# vcfvca.net
KiCad netlist of a schematic drawn in EAGLE
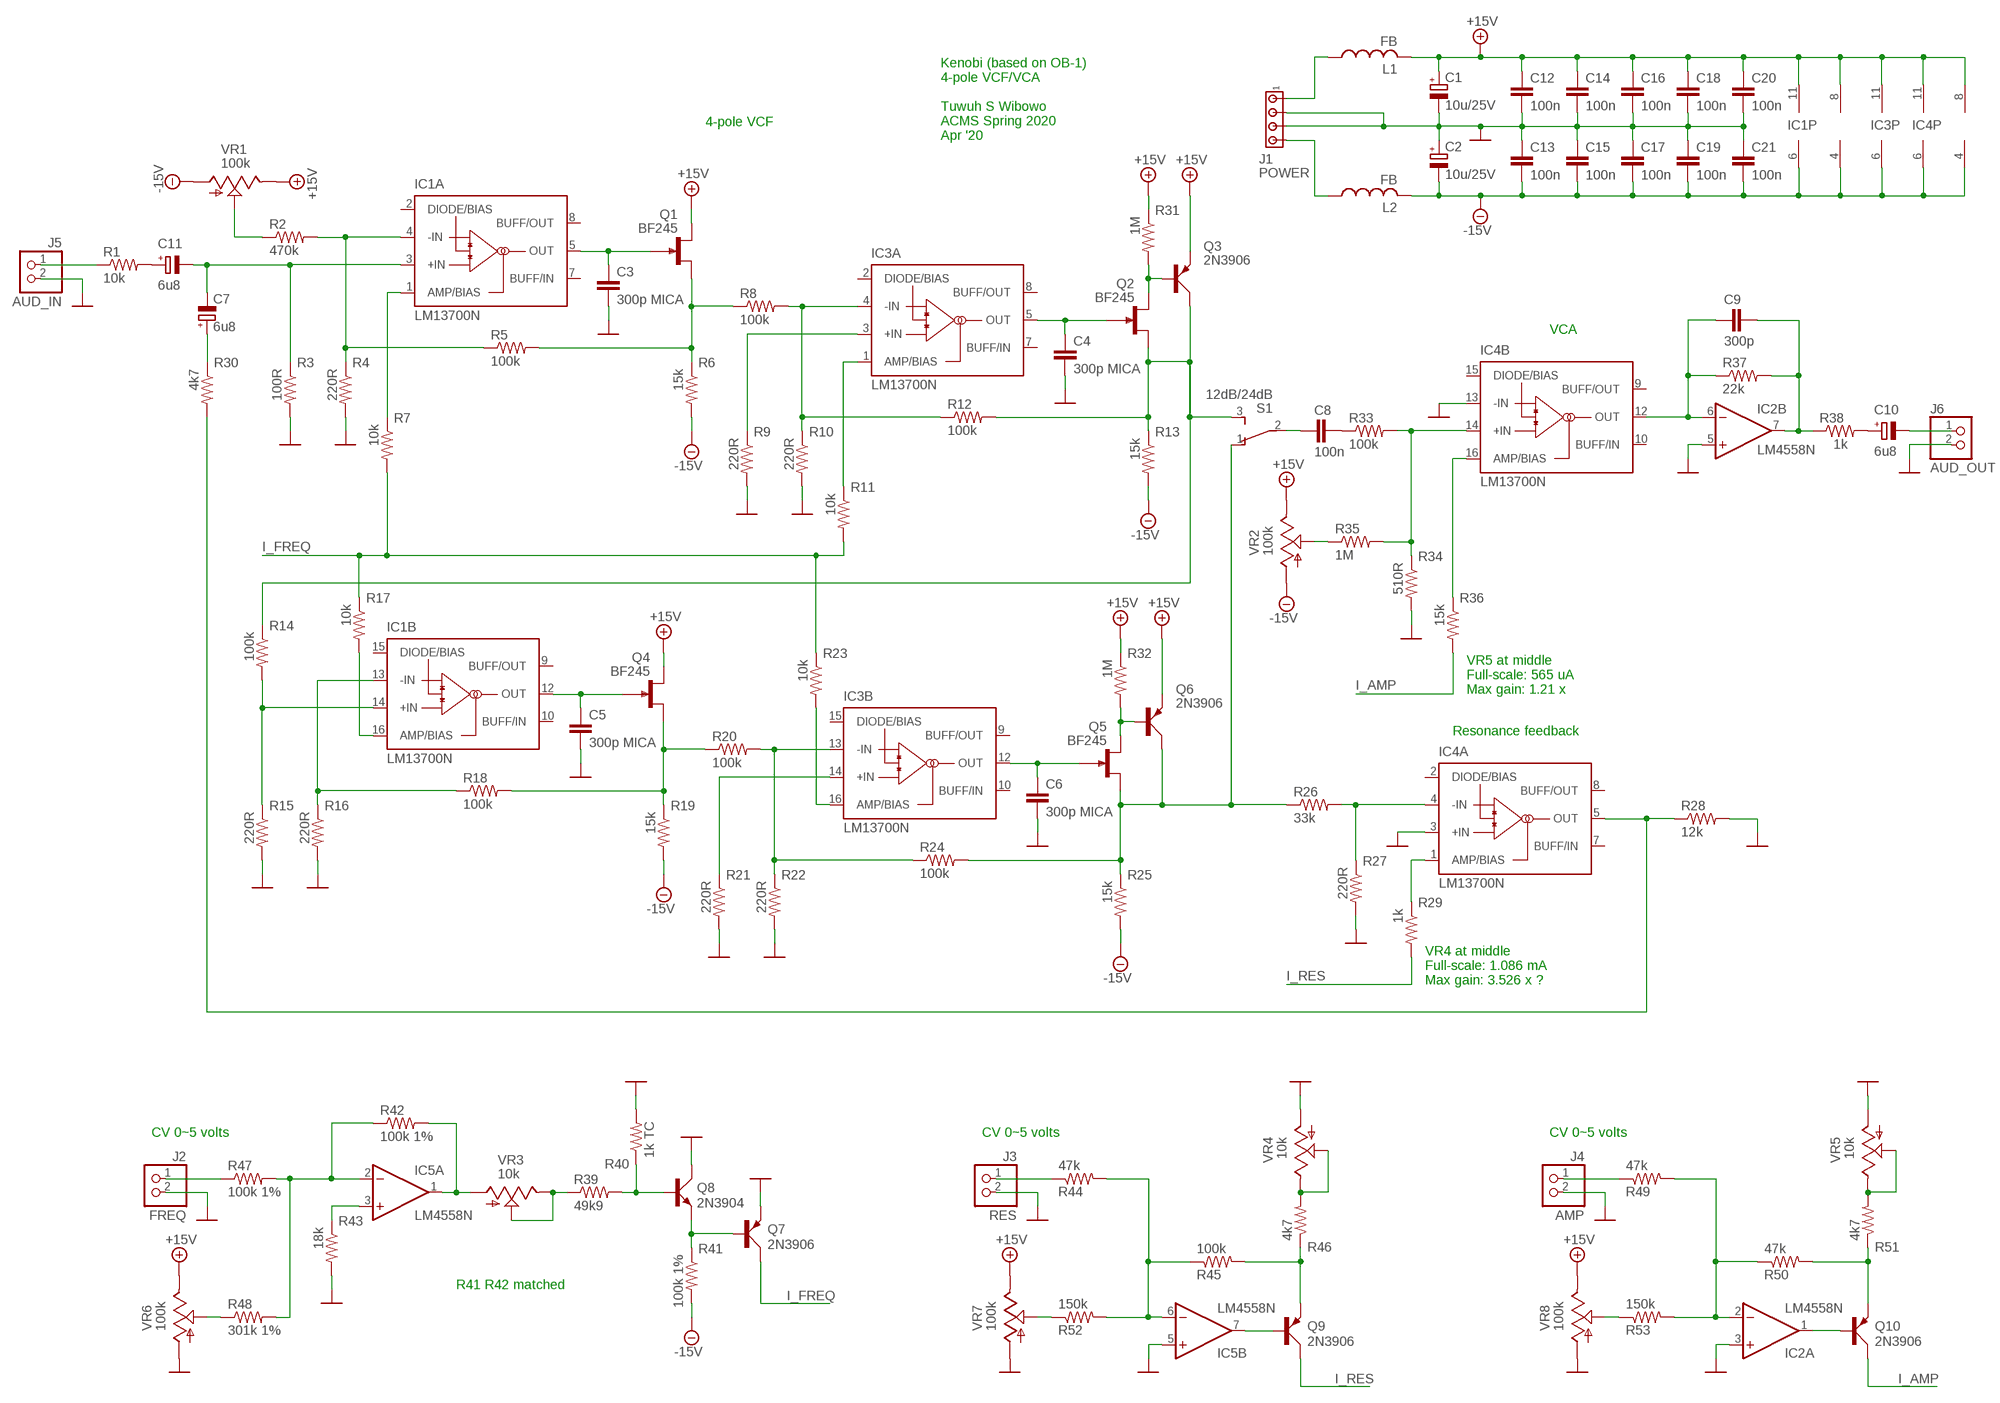
[diagram p0: schematic, sheet 1]

(export (version "E")
  (design (tool "Eeschema 10.0.6"))
  (components
    (comp (ref "C1")
      (value "10u/25V")
      (footprint "eagle-import:E1,8-4")
      (libsource (lib "eagle-import") (part "CPOL-EUE1.8-4"))
    )
    (comp (ref "C2")
      (value "10u/25V")
      (footprint "eagle-import:E1,8-4")
      (libsource (lib "eagle-import") (part "CPOL-EUE1.8-4"))
    )
    (comp (ref "C3")
      (value "300p MICA")
      (footprint "eagle-import:C050-025X075")
      (libsource (lib "eagle-import") (part "C-EU050-025X075"))
    )
    (comp (ref "C4")
      (value "300p MICA")
      (footprint "eagle-import:C050-025X075")
      (libsource (lib "eagle-import") (part "C-EU050-025X075"))
    )
    (comp (ref "C5")
      (value "300p MICA")
      (footprint "eagle-import:C050-025X075")
      (libsource (lib "eagle-import") (part "C-EU050-025X075"))
    )
    (comp (ref "C6")
      (value "300p MICA")
      (footprint "eagle-import:C050-025X075")
      (libsource (lib "eagle-import") (part "C-EU050-025X075"))
    )
    (comp (ref "C7")
      (value "6u8")
      (footprint "eagle-import:E1,8-4")
      (libsource (lib "eagle-import") (part "CPOL-EUE1.8-4"))
    )
    (comp (ref "C8")
      (value "100n")
      (footprint "eagle-import:C050-025X075")
      (libsource (lib "eagle-import") (part "C-EU050-025X075"))
    )
    (comp (ref "C9")
      (value "300p")
      (footprint "eagle-import:C050-025X075")
      (libsource (lib "eagle-import") (part "C-EU050-025X075"))
    )
    (comp (ref "C10")
      (value "6u8")
      (footprint "eagle-import:E1,8-4")
      (libsource (lib "eagle-import") (part "CPOL-EUE1.8-4"))
    )
    (comp (ref "C11")
      (value "6u8")
      (footprint "eagle-import:E1,8-4")
      (libsource (lib "eagle-import") (part "CPOL-EUE1.8-4"))
    )
    (comp (ref "C12")
      (value "100n")
      (footprint "eagle-import:C050-025X075")
      (libsource (lib "eagle-import") (part "C-EU050-025X075"))
    )
    (comp (ref "C13")
      (value "100n")
      (footprint "eagle-import:C050-025X075")
      (libsource (lib "eagle-import") (part "C-EU050-025X075"))
    )
    (comp (ref "C14")
      (value "100n")
      (footprint "eagle-import:C050-025X075")
      (libsource (lib "eagle-import") (part "C-EU050-025X075"))
    )
    (comp (ref "C15")
      (value "100n")
      (footprint "eagle-import:C050-025X075")
      (libsource (lib "eagle-import") (part "C-EU050-025X075"))
    )
    (comp (ref "C16")
      (value "100n")
      (footprint "eagle-import:C050-025X075")
      (libsource (lib "eagle-import") (part "C-EU050-025X075"))
    )
    (comp (ref "C17")
      (value "100n")
      (footprint "eagle-import:C050-025X075")
      (libsource (lib "eagle-import") (part "C-EU050-025X075"))
    )
    (comp (ref "C18")
      (value "100n")
      (footprint "eagle-import:C050-025X075")
      (libsource (lib "eagle-import") (part "C-EU050-025X075"))
    )
    (comp (ref "C19")
      (value "100n")
      (footprint "eagle-import:C050-025X075")
      (libsource (lib "eagle-import") (part "C-EU050-025X075"))
    )
    (comp (ref "C20")
      (value "100n")
      (footprint "eagle-import:C050-025X075")
      (libsource (lib "eagle-import") (part "C-EU050-025X075"))
    )
    (comp (ref "C21")
      (value "100n")
      (footprint "eagle-import:C050-025X075")
      (libsource (lib "eagle-import") (part "C-EU050-025X075"))
    )
    (comp (ref "IC1")
      (value "LM13700N")
      (footprint "eagle-import:DIL16")
      (libsource (lib "eagle-import") (part "LM13600N"))
    )
    (comp (ref "IC2")
      (value "LM4558N")
      (footprint "eagle-import:DIL08")
      (libsource (lib "eagle-import") (part "4558NLM"))
    )
    (comp (ref "IC3")
      (value "LM13700N")
      (footprint "eagle-import:DIL16")
      (libsource (lib "eagle-import") (part "LM13600N"))
    )
    (comp (ref "IC4")
      (value "LM13700N")
      (footprint "eagle-import:DIL16")
      (libsource (lib "eagle-import") (part "LM13600N"))
    )
    (comp (ref "IC5")
      (value "LM4558N")
      (footprint "eagle-import:DIL08")
      (libsource (lib "eagle-import") (part "4558NLM"))
    )
    (comp (ref "J1")
      (value "POWER")
      (footprint "eagle-import:1X4MTA")
      (libsource (lib "eagle-import") (part "MTA04-156"))
    )
    (comp (ref "J2")
      (value "FREQ")
      (footprint "eagle-import:1X02")
      (libsource (lib "eagle-import") (part "PINHD-1X2"))
    )
    (comp (ref "J3")
      (value "RES")
      (footprint "eagle-import:1X02")
      (libsource (lib "eagle-import") (part "PINHD-1X2"))
    )
    (comp (ref "J4")
      (value "AMP")
      (footprint "eagle-import:1X02")
      (libsource (lib "eagle-import") (part "PINHD-1X2"))
    )
    (comp (ref "J5")
      (value "AUD_IN")
      (footprint "eagle-import:1X02")
      (libsource (lib "eagle-import") (part "PINHD-1X2"))
    )
    (comp (ref "J6")
      (value "AUD_OUT")
      (footprint "eagle-import:1X02")
      (libsource (lib "eagle-import") (part "PINHD-1X2"))
    )
    (comp (ref "L1")
      (value "FB")
      (footprint "eagle-import:0207_10")
      (libsource (lib "eagle-import") (part "L-US0207/10"))
    )
    (comp (ref "L2")
      (value "FB")
      (footprint "eagle-import:0207_10")
      (libsource (lib "eagle-import") (part "L-US0207/10"))
    )
    (comp (ref "Q1")
      (value "BF245")
      (footprint "eagle-import:SOT54C")
      (libsource (lib "eagle-import") (part "BF245"))
    )
    (comp (ref "Q2")
      (value "BF245")
      (footprint "eagle-import:SOT54C")
      (libsource (lib "eagle-import") (part "BF245"))
    )
    (comp (ref "Q3")
      (value "2N3906")
      (footprint "eagle-import:TO92D")
      (libsource (lib "eagle-import") (part "2N3906"))
    )
    (comp (ref "Q4")
      (value "BF245")
      (footprint "eagle-import:SOT54C")
      (libsource (lib "eagle-import") (part "BF245"))
    )
    (comp (ref "Q5")
      (value "BF245")
      (footprint "eagle-import:SOT54C")
      (libsource (lib "eagle-import") (part "BF245"))
    )
    (comp (ref "Q6")
      (value "2N3906")
      (footprint "eagle-import:TO92D")
      (libsource (lib "eagle-import") (part "2N3906"))
    )
    (comp (ref "Q7")
      (value "2N3906")
      (footprint "eagle-import:TO92D")
      (libsource (lib "eagle-import") (part "2N3906"))
    )
    (comp (ref "Q8")
      (value "2N3904")
      (footprint "eagle-import:TO92D")
      (libsource (lib "eagle-import") (part "2N3904"))
    )
    (comp (ref "Q9")
      (value "2N3906")
      (footprint "eagle-import:TO92D")
      (libsource (lib "eagle-import") (part "2N3906"))
    )
    (comp (ref "Q10")
      (value "2N3906")
      (footprint "eagle-import:TO92D")
      (libsource (lib "eagle-import") (part "2N3906"))
    )
    (comp (ref "R1")
      (value "10k")
      (footprint "eagle-import:0207_10")
      (libsource (lib "eagle-import") (part "R-US_0207/10"))
    )
    (comp (ref "R2")
      (value "470k")
      (footprint "eagle-import:0207_10")
      (libsource (lib "eagle-import") (part "R-US_0207/10"))
    )
    (comp (ref "R3")
      (value "100R")
      (footprint "eagle-import:0207_10")
      (libsource (lib "eagle-import") (part "R-US_0207/10"))
    )
    (comp (ref "R4")
      (value "220R")
      (footprint "eagle-import:0207_10")
      (libsource (lib "eagle-import") (part "R-US_0207/10"))
    )
    (comp (ref "R5")
      (value "100k")
      (footprint "eagle-import:0207_10")
      (libsource (lib "eagle-import") (part "R-US_0207/10"))
    )
    (comp (ref "R6")
      (value "15k")
      (footprint "eagle-import:0207_10")
      (libsource (lib "eagle-import") (part "R-US_0207/10"))
    )
    (comp (ref "R7")
      (value "10k")
      (footprint "eagle-import:0207_10")
      (libsource (lib "eagle-import") (part "R-US_0207/10"))
    )
    (comp (ref "R8")
      (value "100k")
      (footprint "eagle-import:0207_10")
      (libsource (lib "eagle-import") (part "R-US_0207/10"))
    )
    (comp (ref "R9")
      (value "220R")
      (footprint "eagle-import:0207_10")
      (libsource (lib "eagle-import") (part "R-US_0207/10"))
    )
    (comp (ref "R10")
      (value "220R")
      (footprint "eagle-import:0207_10")
      (libsource (lib "eagle-import") (part "R-US_0207/10"))
    )
    (comp (ref "R11")
      (value "10k")
      (footprint "eagle-import:0207_10")
      (libsource (lib "eagle-import") (part "R-US_0207/10"))
    )
    (comp (ref "R12")
      (value "100k")
      (footprint "eagle-import:0207_10")
      (libsource (lib "eagle-import") (part "R-US_0207/10"))
    )
    (comp (ref "R13")
      (value "15k")
      (footprint "eagle-import:0207_10")
      (libsource (lib "eagle-import") (part "R-US_0207/10"))
    )
    (comp (ref "R14")
      (value "100k")
      (footprint "eagle-import:0207_10")
      (libsource (lib "eagle-import") (part "R-US_0207/10"))
    )
    (comp (ref "R15")
      (value "220R")
      (footprint "eagle-import:0207_10")
      (libsource (lib "eagle-import") (part "R-US_0207/10"))
    )
    (comp (ref "R16")
      (value "220R")
      (footprint "eagle-import:0207_10")
      (libsource (lib "eagle-import") (part "R-US_0207/10"))
    )
    (comp (ref "R17")
      (value "10k")
      (footprint "eagle-import:0207_10")
      (libsource (lib "eagle-import") (part "R-US_0207/10"))
    )
    (comp (ref "R18")
      (value "100k")
      (footprint "eagle-import:0207_10")
      (libsource (lib "eagle-import") (part "R-US_0207/10"))
    )
    (comp (ref "R19")
      (value "15k")
      (footprint "eagle-import:0207_10")
      (libsource (lib "eagle-import") (part "R-US_0207/10"))
    )
    (comp (ref "R20")
      (value "100k")
      (footprint "eagle-import:0207_10")
      (libsource (lib "eagle-import") (part "R-US_0207/10"))
    )
    (comp (ref "R21")
      (value "220R")
      (footprint "eagle-import:0207_10")
      (libsource (lib "eagle-import") (part "R-US_0207/10"))
    )
    (comp (ref "R22")
      (value "220R")
      (footprint "eagle-import:0207_10")
      (libsource (lib "eagle-import") (part "R-US_0207/10"))
    )
    (comp (ref "R23")
      (value "10k")
      (footprint "eagle-import:0207_10")
      (libsource (lib "eagle-import") (part "R-US_0207/10"))
    )
    (comp (ref "R24")
      (value "100k")
      (footprint "eagle-import:0207_10")
      (libsource (lib "eagle-import") (part "R-US_0207/10"))
    )
    (comp (ref "R25")
      (value "15k")
      (footprint "eagle-import:0207_10")
      (libsource (lib "eagle-import") (part "R-US_0207/10"))
    )
    (comp (ref "R26")
      (value "33k")
      (footprint "eagle-import:0207_10")
      (libsource (lib "eagle-import") (part "R-US_0207/10"))
    )
    (comp (ref "R27")
      (value "220R")
      (footprint "eagle-import:0207_10")
      (libsource (lib "eagle-import") (part "R-US_0207/10"))
    )
    (comp (ref "R28")
      (value "12k")
      (footprint "eagle-import:0207_10")
      (libsource (lib "eagle-import") (part "R-US_0207/10"))
    )
    (comp (ref "R29")
      (value "1k")
      (footprint "eagle-import:0207_10")
      (libsource (lib "eagle-import") (part "R-US_0207/10"))
    )
    (comp (ref "R30")
      (value "4k7")
      (footprint "eagle-import:0207_10")
      (libsource (lib "eagle-import") (part "R-US_0207/10"))
    )
    (comp (ref "R31")
      (value "1M")
      (footprint "eagle-import:0207_10")
      (libsource (lib "eagle-import") (part "R-US_0207/10"))
    )
    (comp (ref "R32")
      (value "1M")
      (footprint "eagle-import:0207_10")
      (libsource (lib "eagle-import") (part "R-US_0207/10"))
    )
    (comp (ref "R33")
      (value "100k")
      (footprint "eagle-import:0207_10")
      (libsource (lib "eagle-import") (part "R-US_0207/10"))
    )
    (comp (ref "R34")
      (value "510R")
      (footprint "eagle-import:0207_10")
      (libsource (lib "eagle-import") (part "R-US_0207/10"))
    )
    (comp (ref "R35")
      (value "1M")
      (footprint "eagle-import:0207_10")
      (libsource (lib "eagle-import") (part "R-US_0207/10"))
    )
    (comp (ref "R36")
      (value "15k")
      (footprint "eagle-import:0207_10")
      (libsource (lib "eagle-import") (part "R-US_0207/10"))
    )
    (comp (ref "R37")
      (value "22k")
      (footprint "eagle-import:0207_10")
      (libsource (lib "eagle-import") (part "R-US_0207/10"))
    )
    (comp (ref "R38")
      (value "1k")
      (footprint "eagle-import:0207_10")
      (libsource (lib "eagle-import") (part "R-US_0207/10"))
    )
    (comp (ref "R39")
      (value "49k9")
      (footprint "eagle-import:0207_10")
      (libsource (lib "eagle-import") (part "R-US_0207/10"))
    )
    (comp (ref "R40")
      (value "1k TC")
      (footprint "eagle-import:0207_10")
      (libsource (lib "eagle-import") (part "R-US_0207/10"))
    )
    (comp (ref "R41")
      (value "100k 1%")
      (footprint "eagle-import:0207_10")
      (libsource (lib "eagle-import") (part "R-US_0207/10"))
    )
    (comp (ref "R42")
      (value "100k 1%")
      (footprint "eagle-import:0207_10")
      (libsource (lib "eagle-import") (part "R-US_0207/10"))
    )
    (comp (ref "R43")
      (value "18k")
      (footprint "eagle-import:0207_10")
      (libsource (lib "eagle-import") (part "R-US_0207/10"))
    )
    (comp (ref "R44")
      (value "47k")
      (footprint "eagle-import:0207_10")
      (libsource (lib "eagle-import") (part "R-US_0207/10"))
    )
    (comp (ref "R45")
      (value "100k")
      (footprint "eagle-import:0207_10")
      (libsource (lib "eagle-import") (part "R-US_0207/10"))
    )
    (comp (ref "R46")
      (value "4k7")
      (footprint "eagle-import:0207_10")
      (libsource (lib "eagle-import") (part "R-US_0207/10"))
    )
    (comp (ref "R47")
      (value "100k 1%")
      (footprint "eagle-import:0207_10")
      (libsource (lib "eagle-import") (part "R-US_0207/10"))
    )
    (comp (ref "R48")
      (value "301k 1%")
      (footprint "eagle-import:0207_10")
      (libsource (lib "eagle-import") (part "R-US_0207/10"))
    )
    (comp (ref "R49")
      (value "47k")
      (footprint "eagle-import:0207_10")
      (libsource (lib "eagle-import") (part "R-US_0207/10"))
    )
    (comp (ref "R50")
      (value "47k")
      (footprint "eagle-import:0207_10")
      (libsource (lib "eagle-import") (part "R-US_0207/10"))
    )
    (comp (ref "R51")
      (value "4k7")
      (footprint "eagle-import:0207_10")
      (libsource (lib "eagle-import") (part "R-US_0207/10"))
    )
    (comp (ref "R52")
      (value "150k")
      (footprint "eagle-import:0207_10")
      (libsource (lib "eagle-import") (part "R-US_0207/10"))
    )
    (comp (ref "R53")
      (value "150k")
      (footprint "eagle-import:0207_10")
      (libsource (lib "eagle-import") (part "R-US_0207/10"))
    )
    (comp (ref "S1")
      (value "12dB/24dB")
      (footprint "eagle-import:TL3XPO")
      (libsource (lib "eagle-import") (part "TL36PO"))
    )
    (comp (ref "VR1")
      (value "100k")
      (footprint "eagle-import:S63P")
      (libsource (lib "eagle-import") (part "TRIM_US-S63P"))
    )
    (comp (ref "VR2")
      (value "100k")
      (footprint "eagle-import:S63P")
      (libsource (lib "eagle-import") (part "TRIM_US-S63P"))
    )
    (comp (ref "VR3")
      (value "10k")
      (footprint "eagle-import:S63P")
      (libsource (lib "eagle-import") (part "TRIM_US-S63P"))
    )
    (comp (ref "VR4")
      (value "10k")
      (footprint "eagle-import:S63P")
      (libsource (lib "eagle-import") (part "TRIM_US-S63P"))
    )
    (comp (ref "VR5")
      (value "10k")
      (footprint "eagle-import:S63P")
      (libsource (lib "eagle-import") (part "TRIM_US-S63P"))
    )
    (comp (ref "VR6")
      (value "100k")
      (footprint "eagle-import:B64Y")
      (libsource (lib "eagle-import") (part "TRIM_US-B64Y"))
    )
    (comp (ref "VR7")
      (value "100k")
      (footprint "eagle-import:B64Y")
      (libsource (lib "eagle-import") (part "TRIM_US-B64Y"))
    )
    (comp (ref "VR8")
      (value "100k")
      (footprint "eagle-import:B64Y")
      (libsource (lib "eagle-import") (part "TRIM_US-B64Y"))
    )
  )
  (nets
    (net (code "1") (name "+15V") (class "Default")
      (node (ref "C1") (pin "+") (pinfunction "+_+") (pintype "passive"))
      (node (ref "C12") (pin "1") (pinfunction "1_1") (pintype "passive"))
      (node (ref "C14") (pin "1") (pinfunction "1_1") (pintype "passive"))
      (node (ref "C16") (pin "1") (pinfunction "1_1") (pintype "passive"))
      (node (ref "C18") (pin "1") (pinfunction "1_1") (pintype "passive"))
      (node (ref "C20") (pin "1") (pinfunction "1_1") (pintype "passive"))
      (node (ref "IC1") (pin "11") (pinfunction "V+_11") (pintype "power_in"))
      (node (ref "IC2") (pin "8") (pinfunction "V+_8") (pintype "power_in"))
      (node (ref "IC3") (pin "11") (pinfunction "V+_11") (pintype "power_in"))
      (node (ref "IC4") (pin "11") (pinfunction "V+_11") (pintype "power_in"))
      (node (ref "IC5") (pin "8") (pinfunction "V+_8") (pintype "power_in"))
      (node (ref "L1") (pin "2") (pinfunction "2_2") (pintype "passive"))
      (node (ref "Q1") (pin "D") (pinfunction "D_D") (pintype "passive"))
      (node (ref "Q3") (pin "E") (pinfunction "E_E") (pintype "passive"))
      (node (ref "Q4") (pin "D") (pinfunction "D_D") (pintype "passive"))
      (node (ref "Q6") (pin "E") (pinfunction "E_E") (pintype "passive"))
      (node (ref "R31") (pin "1") (pinfunction "1_1") (pintype "passive"))
      (node (ref "R32") (pin "1") (pinfunction "1_1") (pintype "passive"))
      (node (ref "VR1") (pin "E") (pinfunction "E_E") (pintype "passive"))
      (node (ref "VR2") (pin "E") (pinfunction "E_E") (pintype "passive"))
      (node (ref "VR6") (pin "E") (pinfunction "E_E") (pintype "passive"))
      (node (ref "VR7") (pin "E") (pinfunction "E_E") (pintype "passive"))
      (node (ref "VR8") (pin "E") (pinfunction "E_E") (pintype "passive"))
    )
    (net (code "2") (name "-15V") (class "Default")
      (node (ref "C13") (pin "2") (pinfunction "2_2") (pintype "passive"))
      (node (ref "C15") (pin "2") (pinfunction "2_2") (pintype "passive"))
      (node (ref "C17") (pin "2") (pinfunction "2_2") (pintype "passive"))
      (node (ref "C19") (pin "2") (pinfunction "2_2") (pintype "passive"))
      (node (ref "C2") (pin "-") (pinfunction "-_-") (pintype "passive"))
      (node (ref "C21") (pin "2") (pinfunction "2_2") (pintype "passive"))
      (node (ref "IC1") (pin "6") (pinfunction "V-_6") (pintype "power_in"))
      (node (ref "IC2") (pin "4") (pinfunction "V-_4") (pintype "power_in"))
      (node (ref "IC3") (pin "6") (pinfunction "V-_6") (pintype "power_in"))
      (node (ref "IC4") (pin "6") (pinfunction "V-_6") (pintype "power_in"))
      (node (ref "IC5") (pin "4") (pinfunction "V-_4") (pintype "power_in"))
      (node (ref "L2") (pin "2") (pinfunction "2_2") (pintype "passive"))
      (node (ref "R13") (pin "2") (pinfunction "2_2") (pintype "passive"))
      (node (ref "R19") (pin "2") (pinfunction "2_2") (pintype "passive"))
      (node (ref "R25") (pin "2") (pinfunction "2_2") (pintype "passive"))
      (node (ref "R41") (pin "2") (pinfunction "2_2") (pintype "passive"))
      (node (ref "R6") (pin "2") (pinfunction "2_2") (pintype "passive"))
      (node (ref "VR1") (pin "A") (pinfunction "A_A") (pintype "passive"))
      (node (ref "VR2") (pin "A") (pinfunction "A_A") (pintype "passive"))
    )
    (net (code "3") (name "/I_AMP") (class "Default")
      (node (ref "Q10") (pin "C") (pinfunction "C_C") (pintype "passive"))
      (node (ref "R36") (pin "2") (pinfunction "2_2") (pintype "passive"))
    )
    (net (code "4") (name "/I_FREQ") (class "Default")
      (node (ref "Q7") (pin "C") (pinfunction "C_C") (pintype "passive"))
      (node (ref "R11") (pin "2") (pinfunction "2_2") (pintype "passive"))
      (node (ref "R17") (pin "1") (pinfunction "1_1") (pintype "passive"))
      (node (ref "R23") (pin "1") (pinfunction "1_1") (pintype "passive"))
      (node (ref "R7") (pin "2") (pinfunction "2_2") (pintype "passive"))
    )
    (net (code "5") (name "/I_RES") (class "Default")
      (node (ref "Q9") (pin "C") (pinfunction "C_C") (pintype "passive"))
      (node (ref "R29") (pin "2") (pinfunction "2_2") (pintype "passive"))
    )
    (net (code "6") (name "GND") (class "Default")
      (node (ref "C1") (pin "-") (pinfunction "-_-") (pintype "passive"))
      (node (ref "C12") (pin "2") (pinfunction "2_2") (pintype "passive"))
      (node (ref "C13") (pin "1") (pinfunction "1_1") (pintype "passive"))
      (node (ref "C14") (pin "2") (pinfunction "2_2") (pintype "passive"))
      (node (ref "C15") (pin "1") (pinfunction "1_1") (pintype "passive"))
      (node (ref "C16") (pin "2") (pinfunction "2_2") (pintype "passive"))
      (node (ref "C17") (pin "1") (pinfunction "1_1") (pintype "passive"))
      (node (ref "C18") (pin "2") (pinfunction "2_2") (pintype "passive"))
      (node (ref "C19") (pin "1") (pinfunction "1_1") (pintype "passive"))
      (node (ref "C2") (pin "+") (pinfunction "+_+") (pintype "passive"))
      (node (ref "C20") (pin "2") (pinfunction "2_2") (pintype "passive"))
      (node (ref "C21") (pin "1") (pinfunction "1_1") (pintype "passive"))
      (node (ref "C3") (pin "2") (pinfunction "2_2") (pintype "passive"))
      (node (ref "C4") (pin "2") (pinfunction "2_2") (pintype "passive"))
      (node (ref "C5") (pin "2") (pinfunction "2_2") (pintype "passive"))
      (node (ref "C6") (pin "2") (pinfunction "2_2") (pintype "passive"))
      (node (ref "IC2") (pin "3") (pinfunction "+IN_3") (pintype "input"))
      (node (ref "IC2") (pin "5") (pinfunction "+IN_5") (pintype "input"))
      (node (ref "IC4") (pin "13") (pinfunction "-IN_13") (pintype "input"))
      (node (ref "IC4") (pin "3") (pinfunction "+IN_3") (pintype "input"))
      (node (ref "IC5") (pin "5") (pinfunction "+IN_5") (pintype "input"))
      (node (ref "J1") (pin "2") (pinfunction "2_2") (pintype "passive"))
      (node (ref "J1") (pin "3") (pinfunction "3_3") (pintype "passive"))
      (node (ref "J2") (pin "2") (pinfunction "2_2") (pintype "passive"))
      (node (ref "J3") (pin "2") (pinfunction "2_2") (pintype "passive"))
      (node (ref "J4") (pin "2") (pinfunction "2_2") (pintype "passive"))
      (node (ref "J5") (pin "2") (pinfunction "2_2") (pintype "passive"))
      (node (ref "J6") (pin "2") (pinfunction "2_2") (pintype "passive"))
      (node (ref "Q7") (pin "E") (pinfunction "E_E") (pintype "passive"))
      (node (ref "Q8") (pin "C") (pinfunction "C_C") (pintype "passive"))
      (node (ref "R10") (pin "2") (pinfunction "2_2") (pintype "passive"))
      (node (ref "R15") (pin "2") (pinfunction "2_2") (pintype "passive"))
      (node (ref "R16") (pin "2") (pinfunction "2_2") (pintype "passive"))
      (node (ref "R21") (pin "2") (pinfunction "2_2") (pintype "passive"))
      (node (ref "R22") (pin "2") (pinfunction "2_2") (pintype "passive"))
      (node (ref "R27") (pin "2") (pinfunction "2_2") (pintype "passive"))
      (node (ref "R28") (pin "2") (pinfunction "2_2") (pintype "passive"))
      (node (ref "R3") (pin "2") (pinfunction "2_2") (pintype "passive"))
      (node (ref "R34") (pin "2") (pinfunction "2_2") (pintype "passive"))
      (node (ref "R4") (pin "2") (pinfunction "2_2") (pintype "passive"))
      (node (ref "R40") (pin "2") (pinfunction "2_2") (pintype "passive"))
      (node (ref "R43") (pin "2") (pinfunction "2_2") (pintype "passive"))
      (node (ref "R9") (pin "2") (pinfunction "2_2") (pintype "passive"))
      (node (ref "VR4") (pin "A") (pinfunction "A_A") (pintype "passive"))
      (node (ref "VR5") (pin "A") (pinfunction "A_A") (pintype "passive"))
      (node (ref "VR6") (pin "A") (pinfunction "A_A") (pintype "passive"))
      (node (ref "VR7") (pin "A") (pinfunction "A_A") (pintype "passive"))
      (node (ref "VR8") (pin "A") (pinfunction "A_A") (pintype "passive"))
    )
    (net (code "7") (name "Net-(C7-Pad+)") (class "Default")
      (node (ref "C7") (pin "+") (pinfunction "+_+") (pintype "passive"))
      (node (ref "R30") (pin "1") (pinfunction "1_1") (pintype "passive"))
    )
    (net (code "8") (name "Net-(C8-Pad2)") (class "Default")
      (node (ref "C8") (pin "2") (pinfunction "2_2") (pintype "passive"))
      (node (ref "R33") (pin "1") (pinfunction "1_1") (pintype "passive"))
    )
    (net (code "9") (name "Net-(C10-Pad+)") (class "Default")
      (node (ref "C10") (pin "+") (pinfunction "+_+") (pintype "passive"))
      (node (ref "R38") (pin "2") (pinfunction "2_2") (pintype "passive"))
    )
    (net (code "10") (name "Net-(C10-Pad-)") (class "Default")
      (node (ref "C10") (pin "-") (pinfunction "-_-") (pintype "passive"))
      (node (ref "J6") (pin "1") (pinfunction "1_1") (pintype "passive"))
    )
    (net (code "11") (name "Net-(C11-Pad+)") (class "Default")
      (node (ref "C11") (pin "+") (pinfunction "+_+") (pintype "passive"))
      (node (ref "R1") (pin "2") (pinfunction "2_2") (pintype "passive"))
    )
    (net (code "12") (name "Net-(IC1A-+IN)") (class "Default")
      (node (ref "C11") (pin "-") (pinfunction "-_-") (pintype "passive"))
      (node (ref "C7") (pin "-") (pinfunction "-_-") (pintype "passive"))
      (node (ref "IC1") (pin "3") (pinfunction "+IN_3") (pintype "input"))
      (node (ref "R3") (pin "1") (pinfunction "1_1") (pintype "passive"))
    )
    (net (code "13") (name "Net-(IC1A--IN)") (class "Default")
      (node (ref "IC1") (pin "4") (pinfunction "-IN_4") (pintype "input"))
      (node (ref "R2") (pin "2") (pinfunction "2_2") (pintype "passive"))
      (node (ref "R4") (pin "1") (pinfunction "1_1") (pintype "passive"))
      (node (ref "R5") (pin "1") (pinfunction "1_1") (pintype "passive"))
    )
    (net (code "14") (name "Net-(IC1A-AMP{slash}BIAS)") (class "Default")
      (node (ref "IC1") (pin "1") (pinfunction "AMP/BIAS_1") (pintype "passive"))
      (node (ref "R7") (pin "1") (pinfunction "1_1") (pintype "passive"))
    )
    (net (code "15") (name "Net-(IC1A-OUT)") (class "Default")
      (node (ref "C3") (pin "1") (pinfunction "1_1") (pintype "passive"))
      (node (ref "IC1") (pin "5") (pinfunction "OUT_5") (pintype "output"))
      (node (ref "Q1") (pin "G") (pinfunction "G_G") (pintype "passive"))
    )
    (net (code "16") (name "Net-(IC1B-+IN)") (class "Default")
      (node (ref "IC1") (pin "14") (pinfunction "+IN_14") (pintype "input"))
      (node (ref "R14") (pin "2") (pinfunction "2_2") (pintype "passive"))
      (node (ref "R15") (pin "1") (pinfunction "1_1") (pintype "passive"))
    )
    (net (code "17") (name "Net-(IC1B--IN)") (class "Default")
      (node (ref "IC1") (pin "13") (pinfunction "-IN_13") (pintype "input"))
      (node (ref "R16") (pin "1") (pinfunction "1_1") (pintype "passive"))
      (node (ref "R18") (pin "1") (pinfunction "1_1") (pintype "passive"))
    )
    (net (code "18") (name "Net-(IC1B-AMP{slash}BIAS)") (class "Default")
      (node (ref "IC1") (pin "16") (pinfunction "AMP/BIAS_16") (pintype "passive"))
      (node (ref "R17") (pin "2") (pinfunction "2_2") (pintype "passive"))
    )
    (net (code "19") (name "Net-(IC1B-OUT)") (class "Default")
      (node (ref "C5") (pin "1") (pinfunction "1_1") (pintype "passive"))
      (node (ref "IC1") (pin "12") (pinfunction "OUT_12") (pintype "output"))
      (node (ref "Q4") (pin "G") (pinfunction "G_G") (pintype "passive"))
    )
    (net (code "20") (name "Net-(IC2A--IN)") (class "Default")
      (node (ref "IC2") (pin "2") (pinfunction "-IN_2") (pintype "input"))
      (node (ref "R49") (pin "2") (pinfunction "2_2") (pintype "passive"))
      (node (ref "R50") (pin "1") (pinfunction "1_1") (pintype "passive"))
      (node (ref "R53") (pin "2") (pinfunction "2_2") (pintype "passive"))
    )
    (net (code "21") (name "Net-(IC2A-OUT)") (class "Default")
      (node (ref "IC2") (pin "1") (pinfunction "OUT_1") (pintype "output"))
      (node (ref "Q10") (pin "B") (pinfunction "B_B") (pintype "passive"))
    )
    (net (code "22") (name "Net-(IC2B--IN)") (class "Default")
      (node (ref "C9") (pin "1") (pinfunction "1_1") (pintype "passive"))
      (node (ref "IC2") (pin "6") (pinfunction "-IN_6") (pintype "input"))
      (node (ref "IC4") (pin "12") (pinfunction "OUT_12") (pintype "output"))
      (node (ref "R37") (pin "1") (pinfunction "1_1") (pintype "passive"))
    )
    (net (code "23") (name "Net-(IC2B-OUT)") (class "Default")
      (node (ref "C9") (pin "2") (pinfunction "2_2") (pintype "passive"))
      (node (ref "IC2") (pin "7") (pinfunction "OUT_7") (pintype "output"))
      (node (ref "R37") (pin "2") (pinfunction "2_2") (pintype "passive"))
      (node (ref "R38") (pin "1") (pinfunction "1_1") (pintype "passive"))
    )
    (net (code "24") (name "Net-(IC3A-+IN)") (class "Default")
      (node (ref "IC3") (pin "3") (pinfunction "+IN_3") (pintype "input"))
      (node (ref "R9") (pin "1") (pinfunction "1_1") (pintype "passive"))
    )
    (net (code "25") (name "Net-(IC3A--IN)") (class "Default")
      (node (ref "IC3") (pin "4") (pinfunction "-IN_4") (pintype "input"))
      (node (ref "R10") (pin "1") (pinfunction "1_1") (pintype "passive"))
      (node (ref "R12") (pin "1") (pinfunction "1_1") (pintype "passive"))
      (node (ref "R8") (pin "2") (pinfunction "2_2") (pintype "passive"))
    )
    (net (code "26") (name "Net-(IC3A-AMP{slash}BIAS)") (class "Default")
      (node (ref "IC3") (pin "1") (pinfunction "AMP/BIAS_1") (pintype "passive"))
      (node (ref "R11") (pin "1") (pinfunction "1_1") (pintype "passive"))
    )
    (net (code "27") (name "Net-(IC3A-OUT)") (class "Default")
      (node (ref "C4") (pin "1") (pinfunction "1_1") (pintype "passive"))
      (node (ref "IC3") (pin "5") (pinfunction "OUT_5") (pintype "output"))
      (node (ref "Q2") (pin "G") (pinfunction "G_G") (pintype "passive"))
    )
    (net (code "28") (name "Net-(IC3B-+IN)") (class "Default")
      (node (ref "IC3") (pin "14") (pinfunction "+IN_14") (pintype "input"))
      (node (ref "R21") (pin "1") (pinfunction "1_1") (pintype "passive"))
    )
    (net (code "29") (name "Net-(IC3B--IN)") (class "Default")
      (node (ref "IC3") (pin "13") (pinfunction "-IN_13") (pintype "input"))
      (node (ref "R20") (pin "2") (pinfunction "2_2") (pintype "passive"))
      (node (ref "R22") (pin "1") (pinfunction "1_1") (pintype "passive"))
      (node (ref "R24") (pin "1") (pinfunction "1_1") (pintype "passive"))
    )
    (net (code "30") (name "Net-(IC3B-AMP{slash}BIAS)") (class "Default")
      (node (ref "IC3") (pin "16") (pinfunction "AMP/BIAS_16") (pintype "passive"))
      (node (ref "R23") (pin "2") (pinfunction "2_2") (pintype "passive"))
    )
    (net (code "31") (name "Net-(IC3B-OUT)") (class "Default")
      (node (ref "C6") (pin "1") (pinfunction "1_1") (pintype "passive"))
      (node (ref "IC3") (pin "12") (pinfunction "OUT_12") (pintype "output"))
      (node (ref "Q5") (pin "G") (pinfunction "G_G") (pintype "passive"))
    )
    (net (code "32") (name "Net-(IC4A--IN)") (class "Default")
      (node (ref "IC4") (pin "4") (pinfunction "-IN_4") (pintype "input"))
      (node (ref "R26") (pin "2") (pinfunction "2_2") (pintype "passive"))
      (node (ref "R27") (pin "1") (pinfunction "1_1") (pintype "passive"))
    )
    (net (code "33") (name "Net-(IC4A-AMP{slash}BIAS)") (class "Default")
      (node (ref "IC4") (pin "1") (pinfunction "AMP/BIAS_1") (pintype "passive"))
      (node (ref "R29") (pin "1") (pinfunction "1_1") (pintype "passive"))
    )
    (net (code "34") (name "Net-(IC4A-OUT)") (class "Default")
      (node (ref "IC4") (pin "5") (pinfunction "OUT_5") (pintype "output"))
      (node (ref "R28") (pin "1") (pinfunction "1_1") (pintype "passive"))
      (node (ref "R30") (pin "2") (pinfunction "2_2") (pintype "passive"))
    )
    (net (code "35") (name "Net-(IC4B-+IN)") (class "Default")
      (node (ref "IC4") (pin "14") (pinfunction "+IN_14") (pintype "input"))
      (node (ref "R33") (pin "2") (pinfunction "2_2") (pintype "passive"))
      (node (ref "R34") (pin "1") (pinfunction "1_1") (pintype "passive"))
      (node (ref "R35") (pin "2") (pinfunction "2_2") (pintype "passive"))
    )
    (net (code "36") (name "Net-(IC4B-AMP{slash}BIAS)") (class "Default")
      (node (ref "IC4") (pin "16") (pinfunction "AMP/BIAS_16") (pintype "passive"))
      (node (ref "R36") (pin "1") (pinfunction "1_1") (pintype "passive"))
    )
    (net (code "37") (name "Net-(IC5A-+IN)") (class "Default")
      (node (ref "IC5") (pin "3") (pinfunction "+IN_3") (pintype "input"))
      (node (ref "R43") (pin "1") (pinfunction "1_1") (pintype "passive"))
    )
    (net (code "38") (name "Net-(IC5A--IN)") (class "Default")
      (node (ref "IC5") (pin "2") (pinfunction "-IN_2") (pintype "input"))
      (node (ref "R42") (pin "1") (pinfunction "1_1") (pintype "passive"))
      (node (ref "R47") (pin "2") (pinfunction "2_2") (pintype "passive"))
      (node (ref "R48") (pin "2") (pinfunction "2_2") (pintype "passive"))
    )
    (net (code "39") (name "Net-(IC5A-OUT)") (class "Default")
      (node (ref "IC5") (pin "1") (pinfunction "OUT_1") (pintype "output"))
      (node (ref "R42") (pin "2") (pinfunction "2_2") (pintype "passive"))
      (node (ref "VR3") (pin "A") (pinfunction "A_A") (pintype "passive"))
    )
    (net (code "40") (name "Net-(IC5B--IN)") (class "Default")
      (node (ref "IC5") (pin "6") (pinfunction "-IN_6") (pintype "input"))
      (node (ref "R44") (pin "2") (pinfunction "2_2") (pintype "passive"))
      (node (ref "R45") (pin "1") (pinfunction "1_1") (pintype "passive"))
      (node (ref "R52") (pin "2") (pinfunction "2_2") (pintype "passive"))
    )
    (net (code "41") (name "Net-(IC5B-OUT)") (class "Default")
      (node (ref "IC5") (pin "7") (pinfunction "OUT_7") (pintype "output"))
      (node (ref "Q9") (pin "B") (pinfunction "B_B") (pintype "passive"))
    )
    (net (code "42") (name "Net-(J1-Pad1)") (class "Default")
      (node (ref "J1") (pin "1") (pinfunction "1_1") (pintype "passive"))
      (node (ref "L1") (pin "1") (pinfunction "1_1") (pintype "passive"))
    )
    (net (code "43") (name "Net-(J1-Pad4)") (class "Default")
      (node (ref "J1") (pin "4") (pinfunction "4_4") (pintype "passive"))
      (node (ref "L2") (pin "1") (pinfunction "1_1") (pintype "passive"))
    )
    (net (code "44") (name "Net-(J2-Pad1)") (class "Default")
      (node (ref "J2") (pin "1") (pinfunction "1_1") (pintype "passive"))
      (node (ref "R47") (pin "1") (pinfunction "1_1") (pintype "passive"))
    )
    (net (code "45") (name "Net-(J3-Pad1)") (class "Default")
      (node (ref "J3") (pin "1") (pinfunction "1_1") (pintype "passive"))
      (node (ref "R44") (pin "1") (pinfunction "1_1") (pintype "passive"))
    )
    (net (code "46") (name "Net-(J4-Pad1)") (class "Default")
      (node (ref "J4") (pin "1") (pinfunction "1_1") (pintype "passive"))
      (node (ref "R49") (pin "1") (pinfunction "1_1") (pintype "passive"))
    )
    (net (code "47") (name "Net-(J5-Pad1)") (class "Default")
      (node (ref "J5") (pin "1") (pinfunction "1_1") (pintype "passive"))
      (node (ref "R1") (pin "1") (pinfunction "1_1") (pintype "passive"))
    )
    (net (code "48") (name "Net-(Q1-PadS)") (class "Default")
      (node (ref "Q1") (pin "S") (pinfunction "S_S") (pintype "passive"))
      (node (ref "R5") (pin "2") (pinfunction "2_2") (pintype "passive"))
      (node (ref "R6") (pin "1") (pinfunction "1_1") (pintype "passive"))
      (node (ref "R8") (pin "1") (pinfunction "1_1") (pintype "passive"))
    )
    (net (code "49") (name "Net-(Q2-PadD)") (class "Default")
      (node (ref "Q2") (pin "D") (pinfunction "D_D") (pintype "passive"))
      (node (ref "Q3") (pin "B") (pinfunction "B_B") (pintype "passive"))
      (node (ref "R31") (pin "2") (pinfunction "2_2") (pintype "passive"))
    )
    (net (code "50") (name "Net-(Q4-PadS)") (class "Default")
      (node (ref "Q4") (pin "S") (pinfunction "S_S") (pintype "passive"))
      (node (ref "R18") (pin "2") (pinfunction "2_2") (pintype "passive"))
      (node (ref "R19") (pin "1") (pinfunction "1_1") (pintype "passive"))
      (node (ref "R20") (pin "1") (pinfunction "1_1") (pintype "passive"))
    )
    (net (code "51") (name "Net-(Q5-PadD)") (class "Default")
      (node (ref "Q5") (pin "D") (pinfunction "D_D") (pintype "passive"))
      (node (ref "Q6") (pin "B") (pinfunction "B_B") (pintype "passive"))
      (node (ref "R32") (pin "2") (pinfunction "2_2") (pintype "passive"))
    )
    (net (code "52") (name "Net-(Q7-PadB)") (class "Default")
      (node (ref "Q7") (pin "B") (pinfunction "B_B") (pintype "passive"))
      (node (ref "Q8") (pin "E") (pinfunction "E_E") (pintype "passive"))
      (node (ref "R41") (pin "1") (pinfunction "1_1") (pintype "passive"))
    )
    (net (code "53") (name "Net-(Q8-PadB)") (class "Default")
      (node (ref "Q8") (pin "B") (pinfunction "B_B") (pintype "passive"))
      (node (ref "R39") (pin "2") (pinfunction "2_2") (pintype "passive"))
      (node (ref "R40") (pin "1") (pinfunction "1_1") (pintype "passive"))
    )
    (net (code "54") (name "Net-(Q9-PadE)") (class "Default")
      (node (ref "Q9") (pin "E") (pinfunction "E_E") (pintype "passive"))
      (node (ref "R45") (pin "2") (pinfunction "2_2") (pintype "passive"))
      (node (ref "R46") (pin "1") (pinfunction "1_1") (pintype "passive"))
    )
    (net (code "55") (name "Net-(Q10-PadE)") (class "Default")
      (node (ref "Q10") (pin "E") (pinfunction "E_E") (pintype "passive"))
      (node (ref "R50") (pin "2") (pinfunction "2_2") (pintype "passive"))
      (node (ref "R51") (pin "1") (pinfunction "1_1") (pintype "passive"))
    )
    (net (code "56") (name "Net-(R2-Pad1)") (class "Default")
      (node (ref "R2") (pin "1") (pinfunction "1_1") (pintype "passive"))
      (node (ref "VR1") (pin "S") (pinfunction "S_S") (pintype "passive"))
    )
    (net (code "57") (name "Net-(R35-Pad1)") (class "Default")
      (node (ref "R35") (pin "1") (pinfunction "1_1") (pintype "passive"))
      (node (ref "VR2") (pin "S") (pinfunction "S_S") (pintype "passive"))
    )
    (net (code "58") (name "Net-(R39-Pad1)") (class "Default")
      (node (ref "R39") (pin "1") (pinfunction "1_1") (pintype "passive"))
      (node (ref "VR3") (pin "E") (pinfunction "E_E") (pintype "passive"))
      (node (ref "VR3") (pin "S") (pinfunction "S_S") (pintype "passive"))
    )
    (net (code "59") (name "Net-(R46-Pad2)") (class "Default")
      (node (ref "R46") (pin "2") (pinfunction "2_2") (pintype "passive"))
      (node (ref "VR4") (pin "E") (pinfunction "E_E") (pintype "passive"))
      (node (ref "VR4") (pin "S") (pinfunction "S_S") (pintype "passive"))
    )
    (net (code "60") (name "Net-(R48-Pad1)") (class "Default")
      (node (ref "R48") (pin "1") (pinfunction "1_1") (pintype "passive"))
      (node (ref "VR6") (pin "S") (pinfunction "S_S") (pintype "passive"))
    )
    (net (code "61") (name "Net-(R51-Pad2)") (class "Default")
      (node (ref "R51") (pin "2") (pinfunction "2_2") (pintype "passive"))
      (node (ref "VR5") (pin "E") (pinfunction "E_E") (pintype "passive"))
      (node (ref "VR5") (pin "S") (pinfunction "S_S") (pintype "passive"))
    )
    (net (code "62") (name "Net-(R52-Pad1)") (class "Default")
      (node (ref "R52") (pin "1") (pinfunction "1_1") (pintype "passive"))
      (node (ref "VR7") (pin "S") (pinfunction "S_S") (pintype "passive"))
    )
    (net (code "63") (name "Net-(R53-Pad1)") (class "Default")
      (node (ref "R53") (pin "1") (pinfunction "1_1") (pintype "passive"))
      (node (ref "VR8") (pin "S") (pinfunction "S_S") (pintype "passive"))
    )
    (net (code "64") (name "Net-(S1-O)") (class "Default")
      (node (ref "Q5") (pin "S") (pinfunction "S_S") (pintype "passive"))
      (node (ref "Q6") (pin "C") (pinfunction "C_C") (pintype "passive"))
      (node (ref "R24") (pin "2") (pinfunction "2_2") (pintype "passive"))
      (node (ref "R25") (pin "1") (pinfunction "1_1") (pintype "passive"))
      (node (ref "R26") (pin "1") (pinfunction "1_1") (pintype "passive"))
      (node (ref "S1") (pin "1") (pinfunction "O_1") (pintype "passive"))
    )
    (net (code "65") (name "Net-(S1-P)") (class "Default")
      (node (ref "C8") (pin "1") (pinfunction "1_1") (pintype "passive"))
      (node (ref "S1") (pin "2") (pinfunction "P_2") (pintype "passive"))
    )
    (net (code "66") (name "Net-(S1-S)") (class "Default")
      (node (ref "Q2") (pin "S") (pinfunction "S_S") (pintype "passive"))
      (node (ref "Q3") (pin "C") (pinfunction "C_C") (pintype "passive"))
      (node (ref "R12") (pin "2") (pinfunction "2_2") (pintype "passive"))
      (node (ref "R13") (pin "1") (pinfunction "1_1") (pintype "passive"))
      (node (ref "R14") (pin "1") (pinfunction "1_1") (pintype "passive"))
      (node (ref "S1") (pin "3") (pinfunction "S_3") (pintype "passive"))
    )
    (net (code "67") (name "unconnected-(IC1A-BUFF{slash}IN-Pad7)") (class "Default")
      (node (ref "IC1") (pin "7") (pinfunction "BUFF/IN_7") (pintype "input"))
    )
    (net (code "68") (name "unconnected-(IC1A-BUFF{slash}OUT-Pad8)") (class "Default")
      (node (ref "IC1") (pin "8") (pinfunction "BUFF/OUT_8") (pintype "output"))
    )
    (net (code "69") (name "unconnected-(IC1A-DIODE{slash}BIAS-Pad2)") (class "Default")
      (node (ref "IC1") (pin "2") (pinfunction "DIODE/BIAS_2") (pintype "passive"))
    )
    (net (code "70") (name "unconnected-(IC1B-BUFF{slash}IN-Pad10)") (class "Default")
      (node (ref "IC1") (pin "10") (pinfunction "BUFF/IN_10") (pintype "input"))
    )
    (net (code "71") (name "unconnected-(IC1B-BUFF{slash}OUT-Pad9)") (class "Default")
      (node (ref "IC1") (pin "9") (pinfunction "BUFF/OUT_9") (pintype "output"))
    )
    (net (code "72") (name "unconnected-(IC1B-DIODE{slash}BIAS-Pad15)") (class "Default")
      (node (ref "IC1") (pin "15") (pinfunction "DIODE/BIAS_15") (pintype "passive"))
    )
    (net (code "73") (name "unconnected-(IC3A-BUFF{slash}IN-Pad7)") (class "Default")
      (node (ref "IC3") (pin "7") (pinfunction "BUFF/IN_7") (pintype "input"))
    )
    (net (code "74") (name "unconnected-(IC3A-BUFF{slash}OUT-Pad8)") (class "Default")
      (node (ref "IC3") (pin "8") (pinfunction "BUFF/OUT_8") (pintype "output"))
    )
    (net (code "75") (name "unconnected-(IC3A-DIODE{slash}BIAS-Pad2)") (class "Default")
      (node (ref "IC3") (pin "2") (pinfunction "DIODE/BIAS_2") (pintype "passive"))
    )
    (net (code "76") (name "unconnected-(IC3B-BUFF{slash}IN-Pad10)") (class "Default")
      (node (ref "IC3") (pin "10") (pinfunction "BUFF/IN_10") (pintype "input"))
    )
    (net (code "77") (name "unconnected-(IC3B-BUFF{slash}OUT-Pad9)") (class "Default")
      (node (ref "IC3") (pin "9") (pinfunction "BUFF/OUT_9") (pintype "output"))
    )
    (net (code "78") (name "unconnected-(IC3B-DIODE{slash}BIAS-Pad15)") (class "Default")
      (node (ref "IC3") (pin "15") (pinfunction "DIODE/BIAS_15") (pintype "passive"))
    )
    (net (code "79") (name "unconnected-(IC4A-BUFF{slash}IN-Pad7)") (class "Default")
      (node (ref "IC4") (pin "7") (pinfunction "BUFF/IN_7") (pintype "input"))
    )
    (net (code "80") (name "unconnected-(IC4A-BUFF{slash}OUT-Pad8)") (class "Default")
      (node (ref "IC4") (pin "8") (pinfunction "BUFF/OUT_8") (pintype "output"))
    )
    (net (code "81") (name "unconnected-(IC4A-DIODE{slash}BIAS-Pad2)") (class "Default")
      (node (ref "IC4") (pin "2") (pinfunction "DIODE/BIAS_2") (pintype "passive"))
    )
    (net (code "82") (name "unconnected-(IC4B-BUFF{slash}IN-Pad10)") (class "Default")
      (node (ref "IC4") (pin "10") (pinfunction "BUFF/IN_10") (pintype "input"))
    )
    (net (code "83") (name "unconnected-(IC4B-BUFF{slash}OUT-Pad9)") (class "Default")
      (node (ref "IC4") (pin "9") (pinfunction "BUFF/OUT_9") (pintype "output"))
    )
    (net (code "84") (name "unconnected-(IC4B-DIODE{slash}BIAS-Pad15)") (class "Default")
      (node (ref "IC4") (pin "15") (pinfunction "DIODE/BIAS_15") (pintype "passive"))
    )
  )
)
